# ProPrj_MCC_2024_final_2024-12-02.net
KiCad netlist of a schematic drawn in EasyEDA Pro
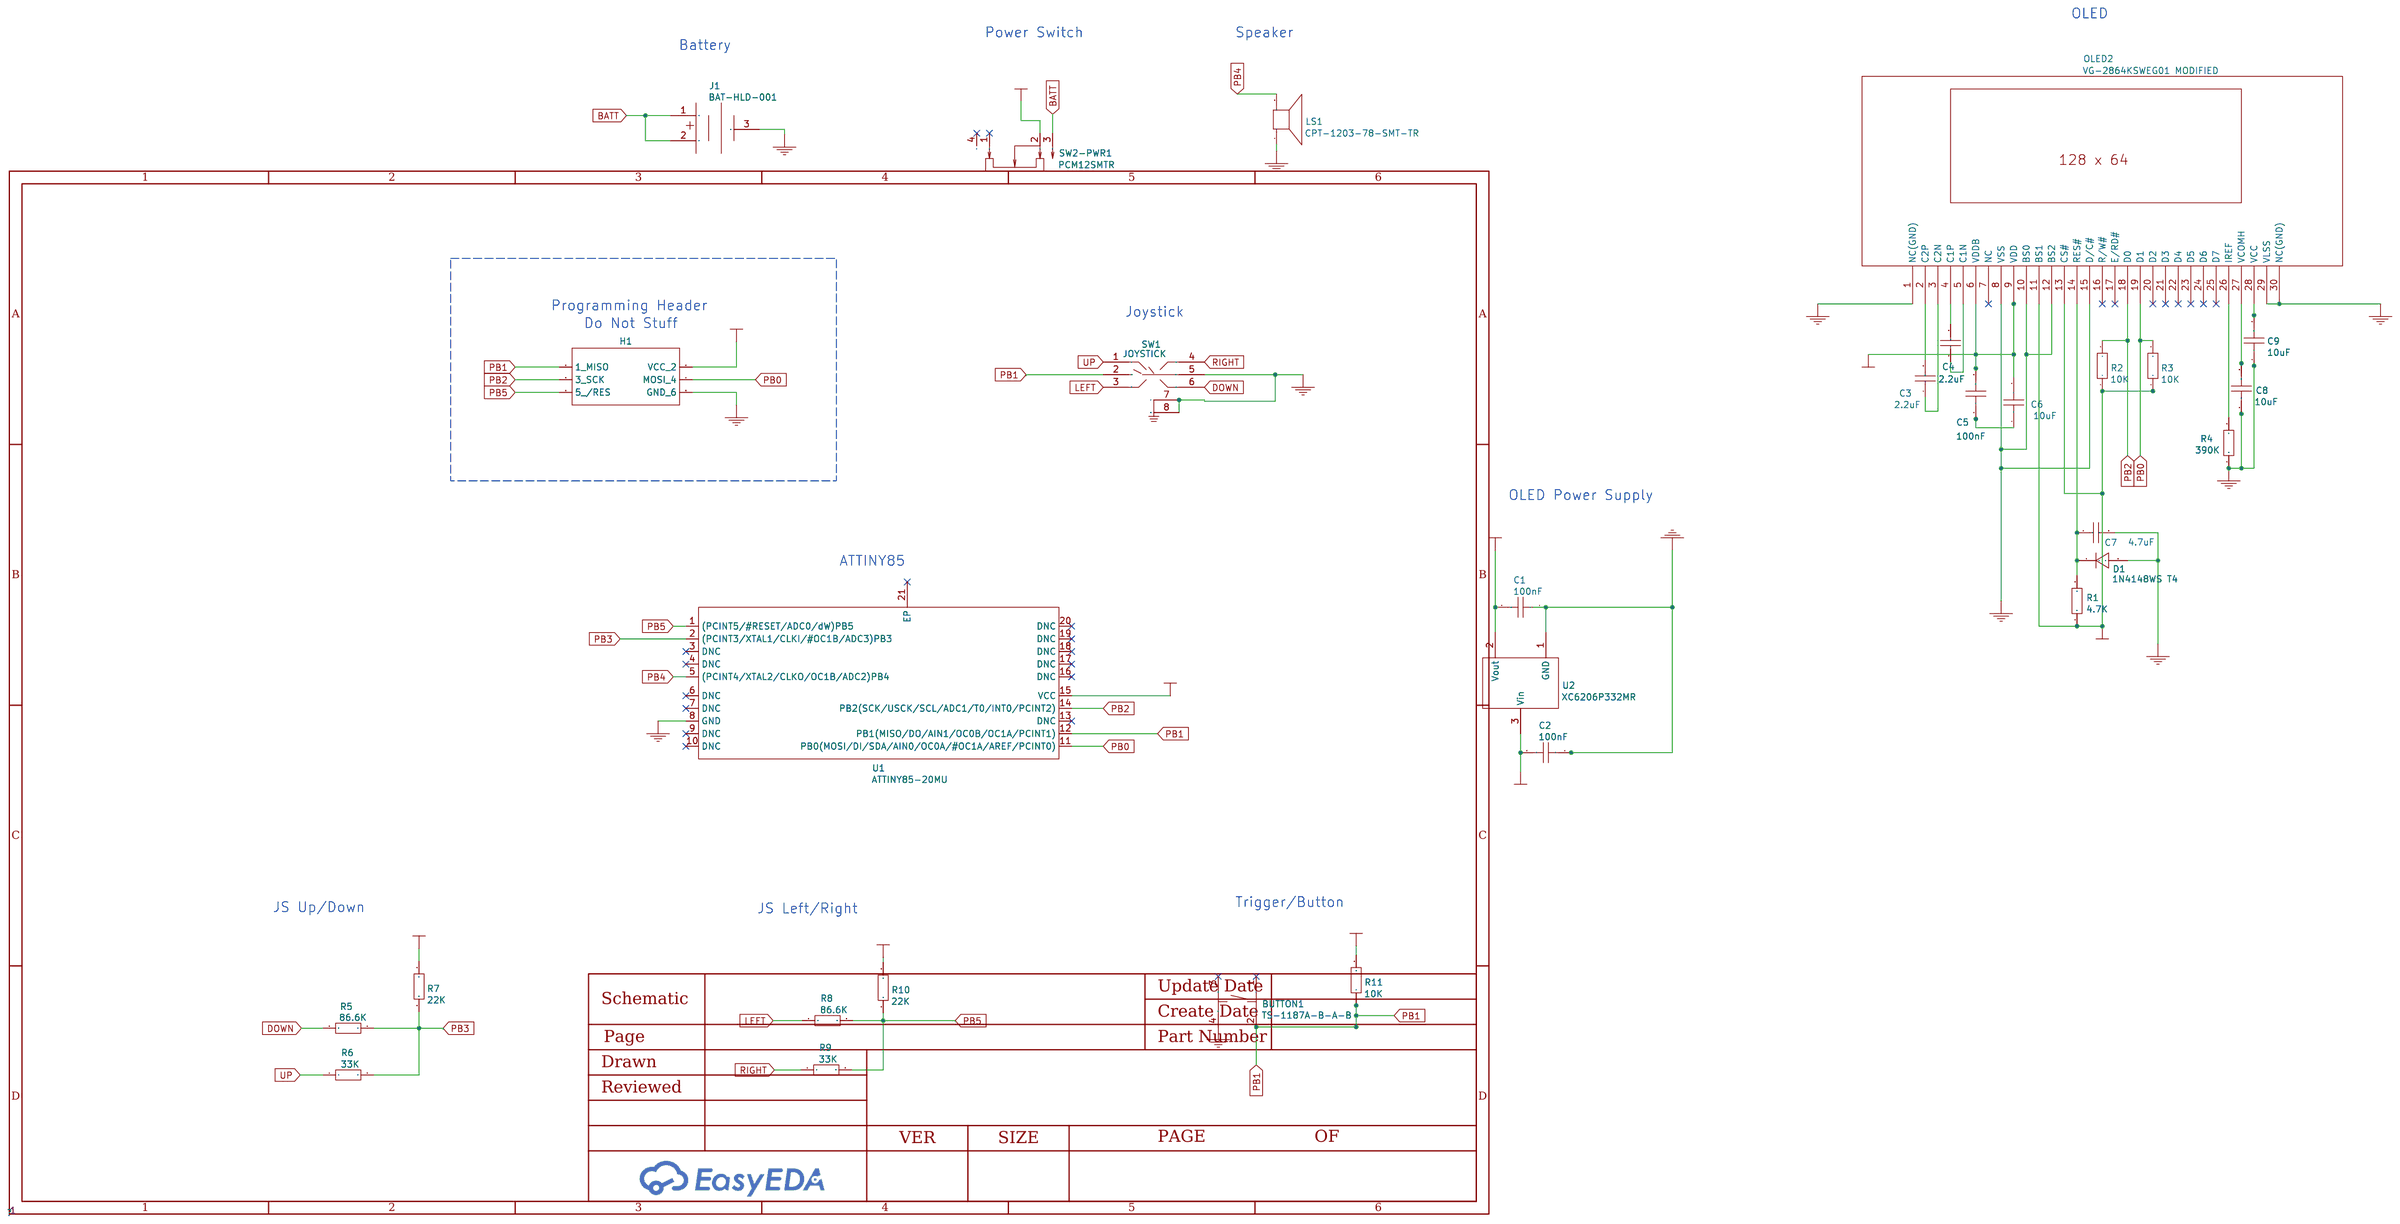
[diagram p0: schematic sheet]

(export (version "E")
  (design (tool "Eeschema 10.0.6"))
  (components
    (comp (ref "BUTTON1")
      (value "TS-1187A-B-A-B")
      (footprint "easyedapro:SW-SMD_4P-L5.1-W5.1-P3.70-LS6.4")
      (fields (field (name "Manufacturer") "XKB Enterprise"))
      (libsource (lib "easyedapro") (part "TS-1187A-B-A-B"))
    )
    (comp (ref "C1")
      (value "100nF")
      (footprint "easyedapro:C0603")
      (fields (field (name "Manufacturer Part") "CC0603KRX7R9BB104") (field (name "Manufacturer") "YAGEO"))
      (libsource (lib "easyedapro") (part "100nF"))
    )
    (comp (ref "C2")
      (value "100nF")
      (footprint "easyedapro:C0603")
      (fields (field (name "Manufacturer Part") "CC0603KRX7R9BB104") (field (name "Manufacturer") "YAGEO"))
      (libsource (lib "easyedapro") (part "100nF"))
    )
    (comp (ref "C3")
      (value "2.2uF")
      (footprint "easyedapro:C0603")
      (fields (field (name "Manufacturer Part") "CL10A225KO8NNNC") (field (name "Manufacturer") "SAMSUNG"))
      (libsource (lib "easyedapro") (part "2.2uF"))
    )
    (comp (ref "C4")
      (value "2.2uF")
      (footprint "easyedapro:C0603")
      (fields (field (name "Manufacturer Part") "CL10A225KO8NNNC") (field (name "Manufacturer") "SAMSUNG"))
      (libsource (lib "easyedapro") (part "2.2uF"))
    )
    (comp (ref "C5")
      (value "100nF")
      (footprint "easyedapro:C0603")
      (fields (field (name "Manufacturer Part") "CC0603KRX7R9BB104") (field (name "Manufacturer") "YAGEO"))
      (libsource (lib "easyedapro") (part "100nF"))
    )
    (comp (ref "C6")
      (value "10uF")
      (footprint "easyedapro:C0603")
      (fields (field (name "Manufacturer Part") "CL10A106KP8NNNC") (field (name "Manufacturer") "SAMSUNG"))
      (libsource (lib "easyedapro") (part "10uF"))
    )
    (comp (ref "C7")
      (value "4.7uF")
      (footprint "easyedapro:C0603")
      (fields (field (name "Manufacturer Part") "CL10A475KO8NNNC") (field (name "Manufacturer") "SAMSUNG"))
      (libsource (lib "easyedapro") (part "4.7uF"))
    )
    (comp (ref "C8")
      (value "10uF")
      (footprint "easyedapro:C0603")
      (fields (field (name "Manufacturer Part") "CL10A106KP8NNNC") (field (name "Manufacturer") "SAMSUNG"))
      (libsource (lib "easyedapro") (part "10uF"))
    )
    (comp (ref "C9")
      (value "10uF")
      (footprint "easyedapro:C0603")
      (fields (field (name "Manufacturer Part") "CL10A106KP8NNNC") (field (name "Manufacturer") "SAMSUNG"))
      (libsource (lib "easyedapro") (part "10uF"))
    )
    (comp (ref "D1")
      (value "1N4148WS T4")
      (footprint "easyedapro:SOD-323_L1.8-W1.3-LS2.5-RD")
      (fields (field (name "Manufacturer") "CJ"))
      (libsource (lib "easyedapro") (part "1N4148WS T4"))
    )
    (comp (ref "H1")
      (value "ISP HEADER")
      (footprint "easyedapro:HDR-TH_6P-P2.54-V-R2-C3-S2.54")
      (fields (field (name "Manufacturer Part") "DS1023-2*3SF11") (field (name "Manufacturer") "CONNFLY"))
      (libsource (lib "easyedapro") (part "ISP HEADER"))
    )
    (comp (ref "J1")
      (value "BAT-HLD-001")
      (footprint "easyedapro:BAT-HLD-001")
      (libsource (lib "easyedapro") (part "BAT-HLD-001"))
    )
    (comp (ref "LS1")
      (value "CPT-1203-78-SMT-TR")
      (footprint "easyedapro:XDCR_CPT-1203-78-SMT-TR")
      (fields (field (name "Manufacturer Part") "CUI Devices"))
      (libsource (lib "easyedapro") (part "CPT-1203-78-SMT-TR"))
    )
    (comp (ref "OLED2")
      (value "VG-2864KSWEG01 MODIFIED")
      (footprint "easyedapro:OLED_0.96-30P-P0.70-12864")
      (fields (field (name "Manufacturer Part") "VG-2864KSWEG01") (field (name "Manufacturer") "WiseChip"))
      (libsource (lib "easyedapro") (part "VG-2864KSWEG01 MODIFIED"))
    )
    (comp (ref "R1")
      (value "4.7K")
      (footprint "easyedapro:R0603")
      (fields (field (name "Manufacturer Part") "0603WAF4701T5E") (field (name "Manufacturer") "UniOhm"))
      (libsource (lib "easyedapro") (part "4.7K"))
    )
    (comp (ref "R2")
      (value "10K")
      (footprint "easyedapro:R0603")
      (fields (field (name "Manufacturer Part") "0603WAF1002T5E") (field (name "Manufacturer") "UniOhm"))
      (libsource (lib "easyedapro") (part "10K"))
    )
    (comp (ref "R3")
      (value "10K")
      (footprint "easyedapro:R0603")
      (fields (field (name "Manufacturer Part") "0603WAF1002T5E") (field (name "Manufacturer") "UniOhm"))
      (libsource (lib "easyedapro") (part "10K"))
    )
    (comp (ref "R4")
      (value "390K")
      (footprint "easyedapro:R0603")
      (fields (field (name "Manufacturer Part") "0603WAF3903T5E") (field (name "Manufacturer") "UniOhm"))
      (libsource (lib "easyedapro") (part "390K"))
    )
    (comp (ref "R5")
      (value "86.6K")
      (footprint "easyedapro:R0603")
      (fields (field (name "Manufacturer Part") "0603WAF8662T5E") (field (name "Manufacturer") "UniOhm"))
      (libsource (lib "easyedapro") (part "86.6K"))
    )
    (comp (ref "R6")
      (value "33K")
      (footprint "easyedapro:R0603")
      (fields (field (name "Manufacturer Part") "0603WAF3302T5E") (field (name "Manufacturer") "UniOhm"))
      (libsource (lib "easyedapro") (part "33K"))
    )
    (comp (ref "R7")
      (value "22K")
      (footprint "easyedapro:R0603")
      (fields (field (name "Manufacturer Part") "0603WAF2202T5E") (field (name "Manufacturer") "UniOhm"))
      (libsource (lib "easyedapro") (part "22K"))
    )
    (comp (ref "R8")
      (value "86.6K")
      (footprint "easyedapro:R0603")
      (fields (field (name "Manufacturer Part") "0603WAF8662T5E") (field (name "Manufacturer") "UniOhm"))
      (libsource (lib "easyedapro") (part "86.6K"))
    )
    (comp (ref "R9")
      (value "33K")
      (footprint "easyedapro:R0603")
      (fields (field (name "Manufacturer Part") "0603WAF3302T5E") (field (name "Manufacturer") "UniOhm"))
      (libsource (lib "easyedapro") (part "33K"))
    )
    (comp (ref "R10")
      (value "22K")
      (footprint "easyedapro:R0603")
      (fields (field (name "Manufacturer Part") "0603WAF2202T5E") (field (name "Manufacturer") "UniOhm"))
      (libsource (lib "easyedapro") (part "22K"))
    )
    (comp (ref "R11")
      (value "10K")
      (footprint "easyedapro:R0603")
      (fields (field (name "Manufacturer Part") "0603WAF1002T5E") (field (name "Manufacturer") "UniOhm"))
      (libsource (lib "easyedapro") (part "10K"))
    )
    (comp (ref "SW1")
      (value "JOYSTICK")
      (footprint "easyedapro:SW-SMD_SKRHADE010")
      (fields (field (name "Manufacturer Part") "SKRHADE011") (field (name "Manufacturer") "ALPS Electric"))
      (libsource (lib "easyedapro") (part "JOYSTICK"))
    )
    (comp (ref "SW2-PWR1")
      (value "PCM12SMTR")
      (footprint "easyedapro:SW-SMD_PCM12SMTR")
      (fields (field (name "Manufacturer") "C&K"))
      (libsource (lib "easyedapro") (part "PCM12SMTR"))
    )
    (comp (ref "U1")
      (value "ATTINY85-20MU")
      (footprint "easyedapro:QFN-20_L4.0-W4.0-P0.50-BL-EP")
      (fields (field (name "Manufacturer") "Microchip Tech"))
      (libsource (lib "easyedapro") (part "ATTINY85-20MU"))
    )
    (comp (ref "U2")
      (value "XC6206P332MR")
      (footprint "easyedapro:SOT-23-3_L2.9-W1.6-P1.90-LS2.8-BR")
      (fields (field (name "Manufacturer") "TOREX"))
      (libsource (lib "easyedapro") (part "XC6206P332MR"))
    )
  )
  (nets
    (net (code "1") (name "3.3V") (class "Default")
      (node (ref "C1") (pin "2") (pinfunction "2_2") (pintype "unspecified"))
      (node (ref "C5") (pin "2") (pinfunction "2_2") (pintype "unspecified"))
      (node (ref "C6") (pin "2") (pinfunction "2_2") (pintype "unspecified"))
      (node (ref "OLED2") (pin "11") (pinfunction "BS1_11") (pintype "unspecified"))
      (node (ref "OLED2") (pin "13") (pinfunction "CS#_13") (pintype "unspecified"))
      (node (ref "OLED2") (pin "6") (pinfunction "VDDB_6") (pintype "unspecified"))
      (node (ref "OLED2") (pin "9") (pinfunction "VDD_9") (pintype "unspecified"))
      (node (ref "R1") (pin "1") (pinfunction "1_1") (pintype "input"))
      (node (ref "R2") (pin "1") (pinfunction "1_1") (pintype "input"))
      (node (ref "R3") (pin "1") (pinfunction "1_1") (pintype "input"))
      (node (ref "U2") (pin "2") (pinfunction "Vout_2") (pintype "unspecified"))
    )
    (net (code "2") (name "BATT") (class "Default")
      (node (ref "J1") (pin "1") (pinfunction "1_1") (pintype "unspecified"))
      (node (ref "J1") (pin "2") (pinfunction "1_2") (pintype "unspecified"))
      (node (ref "SW2-PWR1") (pin "3") (pinfunction "3_3") (pintype "unspecified"))
    )
    (net (code "3") (name "DOWN") (class "Default")
      (node (ref "R5") (pin "2") (pinfunction "2_2") (pintype "input"))
      (node (ref "SW1") (pin "6") (pinfunction "D_6") (pintype "unspecified"))
    )
    (net (code "4") (name "GND") (class "Default")
      (node (ref "BUTTON1") (pin "4") (pinfunction "D_4") (pintype "unspecified"))
      (node (ref "C1") (pin "1") (pinfunction "1_1") (pintype "unspecified"))
      (node (ref "C2") (pin "1") (pinfunction "1_1") (pintype "unspecified"))
      (node (ref "C7") (pin "2") (pinfunction "2_2") (pintype "input"))
      (node (ref "C8") (pin "1") (pinfunction "1_1") (pintype "unspecified"))
      (node (ref "C9") (pin "1") (pinfunction "1_1") (pintype "unspecified"))
      (node (ref "D1") (pin "2") (pinfunction "A_2") (pintype "unspecified"))
      (node (ref "H1") (pin "6") (pinfunction "GND_6_6") (pintype "input"))
      (node (ref "J1") (pin "3") (pinfunction "2_3") (pintype "unspecified"))
      (node (ref "LS1") (pin "N") (pinfunction "N_N") (pintype "bidirectional"))
      (node (ref "OLED2") (pin "1") (pinfunction "NC(GND)_1") (pintype "unspecified"))
      (node (ref "OLED2") (pin "10") (pinfunction "BS0_10") (pintype "unspecified"))
      (node (ref "OLED2") (pin "12") (pinfunction "BS2_12") (pintype "unspecified"))
      (node (ref "OLED2") (pin "15") (pinfunction "D/C#_15") (pintype "unspecified"))
      (node (ref "OLED2") (pin "29") (pinfunction "VLSS_29") (pintype "unspecified"))
      (node (ref "OLED2") (pin "30") (pinfunction "NC(GND)_30") (pintype "unspecified"))
      (node (ref "OLED2") (pin "8") (pinfunction "VSS_8") (pintype "unspecified"))
      (node (ref "R4") (pin "1") (pinfunction "1_1") (pintype "input"))
      (node (ref "SW1") (pin "5") (pinfunction "COM_5") (pintype "unspecified"))
      (node (ref "SW1") (pin "7") (pinfunction "7_7") (pintype "unspecified"))
      (node (ref "SW1") (pin "8") (pinfunction "8_8") (pintype "unspecified"))
      (node (ref "U1") (pin "8") (pinfunction "GND_8") (pintype "unspecified"))
      (node (ref "U2") (pin "1") (pinfunction "GND_1") (pintype "unspecified"))
    )
    (net (code "5") (name "LEFT") (class "Default")
      (node (ref "R8") (pin "1") (pinfunction "1_1") (pintype "input"))
      (node (ref "SW1") (pin "3") (pinfunction "C_3") (pintype "unspecified"))
    )
    (net (code "6") (name "Net-(C5-Pad1)") (class "Default")
      (node (ref "C5") (pin "1") (pinfunction "1_1") (pintype "unspecified"))
      (node (ref "C6") (pin "1") (pinfunction "1_1") (pintype "unspecified"))
    )
    (net (code "7") (name "Net-(D1-K)") (class "Default")
      (node (ref "C7") (pin "1") (pinfunction "1_1") (pintype "input"))
      (node (ref "D1") (pin "1") (pinfunction "K_1") (pintype "unspecified"))
      (node (ref "OLED2") (pin "14") (pinfunction "RES#_14") (pintype "unspecified"))
      (node (ref "R1") (pin "2") (pinfunction "2_2") (pintype "input"))
    )
    (net (code "8") (name "Net-(OLED2-C1N)") (class "Default")
      (node (ref "C4") (pin "1") (pinfunction "1_1") (pintype "input"))
      (node (ref "OLED2") (pin "5") (pinfunction "C1N_5") (pintype "unspecified"))
    )
    (net (code "9") (name "Net-(OLED2-C1P)") (class "Default")
      (node (ref "C4") (pin "2") (pinfunction "2_2") (pintype "input"))
      (node (ref "OLED2") (pin "4") (pinfunction "C1P_4") (pintype "unspecified"))
    )
    (net (code "10") (name "Net-(OLED2-C2N)") (class "Default")
      (node (ref "C3") (pin "1") (pinfunction "1_1") (pintype "input"))
      (node (ref "OLED2") (pin "3") (pinfunction "C2N_3") (pintype "unspecified"))
    )
    (net (code "11") (name "Net-(OLED2-C2P)") (class "Default")
      (node (ref "C3") (pin "2") (pinfunction "2_2") (pintype "input"))
      (node (ref "OLED2") (pin "2") (pinfunction "C2P_2") (pintype "unspecified"))
    )
    (net (code "12") (name "Net-(OLED2-IREF)") (class "Default")
      (node (ref "OLED2") (pin "26") (pinfunction "IREF_26") (pintype "unspecified"))
      (node (ref "R4") (pin "2") (pinfunction "2_2") (pintype "input"))
    )
    (net (code "13") (name "Net-(OLED2-VCC)") (class "Default")
      (node (ref "C9") (pin "2") (pinfunction "2_2") (pintype "unspecified"))
      (node (ref "OLED2") (pin "28") (pinfunction "VCC_28") (pintype "unspecified"))
    )
    (net (code "14") (name "Net-(OLED2-VCOMH)") (class "Default")
      (node (ref "C8") (pin "2") (pinfunction "2_2") (pintype "unspecified"))
      (node (ref "OLED2") (pin "27") (pinfunction "VCOMH_27") (pintype "unspecified"))
    )
    (net (code "15") (name "PB0") (class "Default")
      (node (ref "H1") (pin "4") (pinfunction "MOSI_4_4") (pintype "input"))
      (node (ref "OLED2") (pin "19") (pinfunction "D1_19") (pintype "unspecified"))
      (node (ref "R3") (pin "2") (pinfunction "2_2") (pintype "input"))
      (node (ref "U1") (pin "11") (pinfunction "PB0(MOSI/DI/SDA/AIN0/OC0A/#OC1A/AREF/PCINT0)_11") (pintype "unspecified"))
    )
    (net (code "16") (name "PB1") (class "Default")
      (node (ref "BUTTON1") (pin "2") (pinfunction "B_2") (pintype "unspecified"))
      (node (ref "H1") (pin "1") (pinfunction "1_MISO_1") (pintype "input"))
      (node (ref "R11") (pin "1") (pinfunction "1_1") (pintype "input"))
      (node (ref "SW1") (pin "2") (pinfunction "CEN_2") (pintype "unspecified"))
      (node (ref "U1") (pin "12") (pinfunction "PB1(MISO/DO/AIN1/OC0B/OC1A/PCINT1)_12") (pintype "unspecified"))
    )
    (net (code "17") (name "PB2") (class "Default")
      (node (ref "H1") (pin "3") (pinfunction "3_SCK_3") (pintype "input"))
      (node (ref "OLED2") (pin "18") (pinfunction "D0_18") (pintype "unspecified"))
      (node (ref "R2") (pin "2") (pinfunction "2_2") (pintype "input"))
      (node (ref "U1") (pin "14") (pinfunction "PB2(SCK/USCK/SCL/ADC1/T0/INT0/PCINT2)_14") (pintype "unspecified"))
    )
    (net (code "18") (name "PB3") (class "Default")
      (node (ref "R5") (pin "1") (pinfunction "1_1") (pintype "input"))
      (node (ref "R6") (pin "2") (pinfunction "2_2") (pintype "input"))
      (node (ref "R7") (pin "2") (pinfunction "2_2") (pintype "input"))
      (node (ref "U1") (pin "2") (pinfunction "(PCINT3/XTAL1/CLKI/#OC1B/ADC3)PB3_2") (pintype "unspecified"))
    )
    (net (code "19") (name "PB4") (class "Default")
      (node (ref "LS1") (pin "P") (pinfunction "P_P") (pintype "bidirectional"))
      (node (ref "U1") (pin "5") (pinfunction "(PCINT4/XTAL2/CLKO/OC1B/ADC2)PB4_5") (pintype "unspecified"))
    )
    (net (code "20") (name "PB5") (class "Default")
      (node (ref "H1") (pin "5") (pinfunction "5_/RES_5") (pintype "input"))
      (node (ref "R10") (pin "1") (pinfunction "1_1") (pintype "input"))
      (node (ref "R8") (pin "2") (pinfunction "2_2") (pintype "input"))
      (node (ref "R9") (pin "2") (pinfunction "2_2") (pintype "input"))
      (node (ref "U1") (pin "1") (pinfunction "(PCINT5/#RESET/ADC0/dW)PB5_1") (pintype "unspecified"))
    )
    (net (code "21") (name "RIGHT") (class "Default")
      (node (ref "R9") (pin "1") (pinfunction "1_1") (pintype "input"))
      (node (ref "SW1") (pin "4") (pinfunction "B_4") (pintype "unspecified"))
    )
    (net (code "22") (name "UP") (class "Default")
      (node (ref "R6") (pin "1") (pinfunction "1_1") (pintype "input"))
      (node (ref "SW1") (pin "1") (pinfunction "A_1") (pintype "unspecified"))
    )
    (net (code "23") (name "VCC") (class "Default")
      (node (ref "C2") (pin "2") (pinfunction "2_2") (pintype "unspecified"))
      (node (ref "H1") (pin "2") (pinfunction "VCC_2_2") (pintype "input"))
      (node (ref "R10") (pin "2") (pinfunction "2_2") (pintype "input"))
      (node (ref "R11") (pin "2") (pinfunction "2_2") (pintype "input"))
      (node (ref "R7") (pin "1") (pinfunction "1_1") (pintype "input"))
      (node (ref "SW2-PWR1") (pin "2") (pinfunction "2_2") (pintype "unspecified"))
      (node (ref "U1") (pin "15") (pinfunction "VCC_15") (pintype "unspecified"))
      (node (ref "U2") (pin "3") (pinfunction "Vin_3") (pintype "unspecified"))
    )
    (net (code "24") (name "unconnected-(BUTTON1-A-Pad1)") (class "Default")
      (node (ref "BUTTON1") (pin "1") (pinfunction "A_1") (pintype "unspecified+no_connect"))
    )
    (net (code "25") (name "unconnected-(BUTTON1-C-Pad3)") (class "Default")
      (node (ref "BUTTON1") (pin "3") (pinfunction "C_3") (pintype "unspecified+no_connect"))
    )
    (net (code "26") (name "unconnected-(OLED2-D2-Pad20)") (class "Default")
      (node (ref "OLED2") (pin "20") (pinfunction "D2_20") (pintype "unspecified+no_connect"))
    )
    (net (code "27") (name "unconnected-(OLED2-D3-Pad21)") (class "Default")
      (node (ref "OLED2") (pin "21") (pinfunction "D3_21") (pintype "unspecified+no_connect"))
    )
    (net (code "28") (name "unconnected-(OLED2-D4-Pad22)") (class "Default")
      (node (ref "OLED2") (pin "22") (pinfunction "D4_22") (pintype "unspecified+no_connect"))
    )
    (net (code "29") (name "unconnected-(OLED2-D5-Pad23)") (class "Default")
      (node (ref "OLED2") (pin "23") (pinfunction "D5_23") (pintype "unspecified+no_connect"))
    )
    (net (code "30") (name "unconnected-(OLED2-D6-Pad24)") (class "Default")
      (node (ref "OLED2") (pin "24") (pinfunction "D6_24") (pintype "unspecified+no_connect"))
    )
    (net (code "31") (name "unconnected-(OLED2-D7-Pad25)") (class "Default")
      (node (ref "OLED2") (pin "25") (pinfunction "D7_25") (pintype "unspecified+no_connect"))
    )
    (net (code "32") (name "unconnected-(OLED2-E{slash}RD#-Pad17)") (class "Default")
      (node (ref "OLED2") (pin "17") (pinfunction "E/RD#_17") (pintype "unspecified+no_connect"))
    )
    (net (code "33") (name "unconnected-(OLED2-NC-Pad7)") (class "Default")
      (node (ref "OLED2") (pin "7") (pinfunction "NC_7") (pintype "unspecified+no_connect"))
    )
    (net (code "34") (name "unconnected-(OLED2-R{slash}W#-Pad16)") (class "Default")
      (node (ref "OLED2") (pin "16") (pinfunction "R/W#_16") (pintype "unspecified+no_connect"))
    )
    (net (code "35") (name "unconnected-(SW2-PWR1-Pad1)") (class "Default")
      (node (ref "SW2-PWR1") (pin "1") (pinfunction "1_1") (pintype "unspecified+no_connect"))
    )
    (net (code "36") (name "unconnected-(SW2-PWR1-Pad4)") (class "Default")
      (node (ref "SW2-PWR1") (pin "4") (pinfunction "4_4") (pintype "unspecified+no_connect"))
    )
    (net (code "37") (name "unconnected-(U1-DNC-Pad3)") (class "Default")
      (node (ref "U1") (pin "3") (pinfunction "DNC_3") (pintype "unspecified+no_connect"))
    )
    (net (code "38") (name "unconnected-(U1-DNC-Pad4)") (class "Default")
      (node (ref "U1") (pin "4") (pinfunction "DNC_4") (pintype "unspecified+no_connect"))
    )
    (net (code "39") (name "unconnected-(U1-DNC-Pad6)") (class "Default")
      (node (ref "U1") (pin "6") (pinfunction "DNC_6") (pintype "unspecified+no_connect"))
    )
    (net (code "40") (name "unconnected-(U1-DNC-Pad7)") (class "Default")
      (node (ref "U1") (pin "7") (pinfunction "DNC_7") (pintype "unspecified+no_connect"))
    )
    (net (code "41") (name "unconnected-(U1-DNC-Pad9)") (class "Default")
      (node (ref "U1") (pin "9") (pinfunction "DNC_9") (pintype "unspecified+no_connect"))
    )
    (net (code "42") (name "unconnected-(U1-DNC-Pad10)") (class "Default")
      (node (ref "U1") (pin "10") (pinfunction "DNC_10") (pintype "unspecified+no_connect"))
    )
    (net (code "43") (name "unconnected-(U1-DNC-Pad13)") (class "Default")
      (node (ref "U1") (pin "13") (pinfunction "DNC_13") (pintype "unspecified+no_connect"))
    )
    (net (code "44") (name "unconnected-(U1-DNC-Pad16)") (class "Default")
      (node (ref "U1") (pin "16") (pinfunction "DNC_16") (pintype "unspecified+no_connect"))
    )
    (net (code "45") (name "unconnected-(U1-DNC-Pad17)") (class "Default")
      (node (ref "U1") (pin "17") (pinfunction "DNC_17") (pintype "unspecified+no_connect"))
    )
    (net (code "46") (name "unconnected-(U1-DNC-Pad18)") (class "Default")
      (node (ref "U1") (pin "18") (pinfunction "DNC_18") (pintype "unspecified+no_connect"))
    )
    (net (code "47") (name "unconnected-(U1-DNC-Pad19)") (class "Default")
      (node (ref "U1") (pin "19") (pinfunction "DNC_19") (pintype "unspecified+no_connect"))
    )
    (net (code "48") (name "unconnected-(U1-DNC-Pad20)") (class "Default")
      (node (ref "U1") (pin "20") (pinfunction "DNC_20") (pintype "unspecified+no_connect"))
    )
    (net (code "49") (name "unconnected-(U1-EP-Pad21)") (class "Default")
      (node (ref "U1") (pin "21") (pinfunction "EP_21") (pintype "unspecified+no_connect"))
    )
  )
)
